# PX4FMUv2_4_6_2.net
KiCad netlist of a schematic drawn in Altium Designer
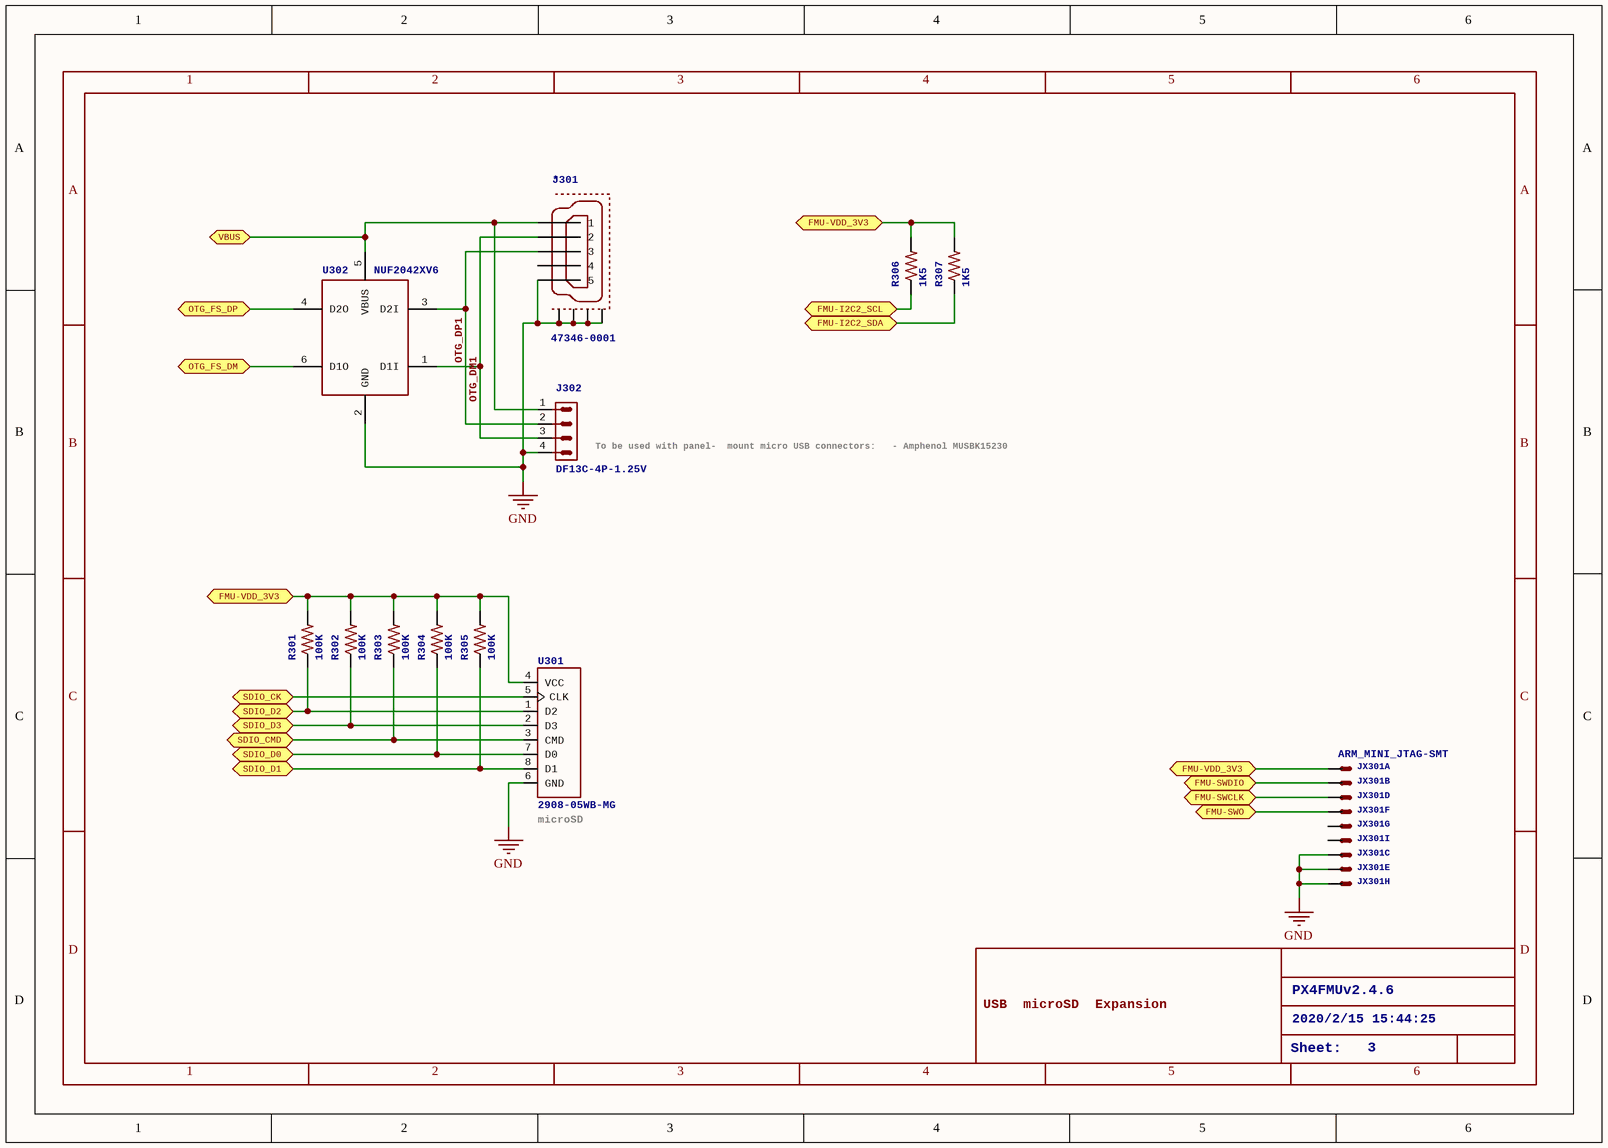
[diagram p0: PX4FMUv2.4.6_2.SchDoc]

(export (version "E")
  (design (tool "Eeschema 10.0.6"))
  (components
    (comp (ref "J301")
      (value "47346-0001")
      (footprint "MOLEX-47346-0001")
      (description "MICRO USB B, BOTTOM MOUNT")
      (fields (field (name "NAME") "*"))
      (libsource (lib "pixhawk2") (part "MOLEX-47346-0001"))
    )
    (comp (ref "J302")
      (value "DF13C-4P-1.25V")
      (footprint "DF13C-4P-1.25V")
      (description "DF13-4P 1.25mm Pitch Miniature Crimping Connector.")
      (fields (field (name "PARTNO") "DF13C-4P-1.25V(20)") (field (name "LIBRARYNAME") "con-hirose-df13"))
      (libsource (lib "con-hirose-df13") (part "DF13-4P-1.25V"))
    )
    (comp (ref "JX301")
      (value "ARM_MINI_JTAG-SMT")
      (footprint "FTSH-105-01-XXX-DV-K")
      (description "CONNECTORwire to board 1.25 mm (.049 inch) pitch header")
      (fields (field (name "PARTNO") "M50-3900542"))
      (libsource (lib "pixhawk2") (part "ARM_MINI_JTAG-SMT"))
    )
    (comp (ref "R301")
      (value "100K")
      (footprint "0402-RES")
      (fields (field (name "PARTNO") "RC0402FR-07100KL"))
      (libsource (lib "pixhawk2") (part "RESISTOR0402-RES"))
    )
    (comp (ref "R302")
      (value "100K")
      (footprint "0402-RES")
      (fields (field (name "PARTNO") "RC0402FR-07100KL"))
      (libsource (lib "pixhawk2") (part "RESISTOR0402-RES"))
    )
    (comp (ref "R303")
      (value "100K")
      (footprint "0402-RES")
      (fields (field (name "PARTNO") "RC0402FR-07100KL"))
      (libsource (lib "pixhawk2") (part "RESISTOR0402-RES"))
    )
    (comp (ref "R304")
      (value "100K")
      (footprint "0402-RES")
      (fields (field (name "PARTNO") "RC0402FR-07100KL"))
      (libsource (lib "pixhawk2") (part "RESISTOR0402-RES"))
    )
    (comp (ref "R305")
      (value "100K")
      (footprint "0402-RES")
      (fields (field (name "PARTNO") "RC0402FR-07100KL"))
      (libsource (lib "pixhawk2") (part "RESISTOR0402-RES"))
    )
    (comp (ref "R306")
      (value "1K5")
      (footprint "0402-RES")
      (fields (field (name "PARTNO") "RC0402FR-071K5L"))
      (libsource (lib "pixhawk2") (part "RESISTOR0402-RES"))
    )
    (comp (ref "R307")
      (value "1K5")
      (footprint "0402-RES")
      (fields (field (name "PARTNO") "RC0402FR-071K5L"))
      (libsource (lib "pixhawk2") (part "RESISTOR0402-RES"))
    )
    (comp (ref "U301")
      (value "2908-05WB-MG")
      (footprint "MICROSD")
      (libsource (lib "baseboard") (part "MICROSDSDI"))
    )
    (comp (ref "U302")
      (value "NUF2042XV6")
      (footprint "SOT563-6")
      (fields (field (name "PARTNO") "NUF2042XV6T1G"))
      (libsource (lib "pixhawk2") (part "NUF2042XV6"))
    )
  )
  (nets
    (net (code "1") (name "/FMU-I2C2_SCL") (class "Default")
      (node (ref "R306") (pin "P$1") (pinfunction "1_P$1") (pintype "passive"))
    )
    (net (code "2") (name "/FMU-I2C2_SDA") (class "Default")
      (node (ref "R307") (pin "P$1") (pinfunction "1_P$1") (pintype "passive"))
    )
    (net (code "3") (name "/FMU-SWCLK") (class "Default")
      (node (ref "JX301") (pin "4") (pinfunction "S_4") (pintype "passive"))
    )
    (net (code "4") (name "/FMU-SWDIO") (class "Default")
      (node (ref "JX301") (pin "2") (pinfunction "S_2") (pintype "passive"))
    )
    (net (code "5") (name "/FMU-SWO") (class "Default")
      (node (ref "JX301") (pin "6") (pinfunction "S_6") (pintype "passive"))
    )
    (net (code "6") (name "/FMU-VDD_3V3") (class "Default")
      (node (ref "JX301") (pin "1") (pinfunction "S_1") (pintype "passive"))
      (node (ref "R301") (pin "P$2") (pinfunction "2_P$2") (pintype "passive"))
      (node (ref "R302") (pin "P$2") (pinfunction "2_P$2") (pintype "passive"))
      (node (ref "R303") (pin "P$2") (pinfunction "2_P$2") (pintype "passive"))
      (node (ref "R304") (pin "P$2") (pinfunction "2_P$2") (pintype "passive"))
      (node (ref "R305") (pin "P$2") (pinfunction "2_P$2") (pintype "passive"))
      (node (ref "R306") (pin "P$2") (pinfunction "2_P$2") (pintype "passive"))
      (node (ref "R307") (pin "P$2") (pinfunction "2_P$2") (pintype "passive"))
      (node (ref "U301") (pin "4") (pinfunction "VCC_4") (pintype "passive"))
    )
    (net (code "7") (name "/OTG_DM1") (class "Default")
      (node (ref "J301") (pin "D-") (pinfunction "2_D-") (pintype "passive"))
      (node (ref "J302") (pin "3") (pinfunction "3_3") (pintype "passive"))
      (node (ref "U302") (pin "1") (pinfunction "D1I_1") (pintype "passive"))
    )
    (net (code "8") (name "/OTG_DP1") (class "Default")
      (node (ref "J301") (pin "D+") (pinfunction "3_D+") (pintype "passive"))
      (node (ref "J302") (pin "2") (pinfunction "2_2") (pintype "passive"))
      (node (ref "U302") (pin "3") (pinfunction "D2I_3") (pintype "passive"))
    )
    (net (code "9") (name "/OTG_FS_DM") (class "Default")
      (node (ref "U302") (pin "6") (pinfunction "D1O_6") (pintype "passive"))
    )
    (net (code "10") (name "/OTG_FS_DP") (class "Default")
      (node (ref "U302") (pin "4") (pinfunction "D2O_4") (pintype "passive"))
    )
    (net (code "11") (name "/SDIO_CK") (class "Default")
      (node (ref "U301") (pin "5") (pinfunction "CLK_5") (pintype "passive"))
    )
    (net (code "12") (name "/SDIO_CMD") (class "Default")
      (node (ref "R303") (pin "P$1") (pinfunction "1_P$1") (pintype "passive"))
      (node (ref "U301") (pin "3") (pinfunction "CMD_3") (pintype "passive"))
    )
    (net (code "13") (name "/SDIO_D0") (class "Default")
      (node (ref "R304") (pin "P$1") (pinfunction "1_P$1") (pintype "passive"))
      (node (ref "U301") (pin "7") (pinfunction "D0_7") (pintype "passive"))
    )
    (net (code "14") (name "/SDIO_D1") (class "Default")
      (node (ref "R305") (pin "P$1") (pinfunction "1_P$1") (pintype "passive"))
      (node (ref "U301") (pin "8") (pinfunction "D1_8") (pintype "passive"))
    )
    (net (code "15") (name "/SDIO_D2") (class "Default")
      (node (ref "R301") (pin "P$1") (pinfunction "1_P$1") (pintype "passive"))
      (node (ref "U301") (pin "1") (pinfunction "D2_1") (pintype "passive"))
    )
    (net (code "16") (name "/SDIO_D3") (class "Default")
      (node (ref "R302") (pin "P$1") (pinfunction "1_P$1") (pintype "passive"))
      (node (ref "U301") (pin "2") (pinfunction "D3_2") (pintype "passive"))
    )
    (net (code "17") (name "/VBUS") (class "Default")
      (node (ref "J301") (pin "VBUS") (pinfunction "1_VBUS") (pintype "open_emitter"))
      (node (ref "J302") (pin "1") (pinfunction "1_1") (pintype "passive"))
      (node (ref "U302") (pin "5") (pinfunction "VBUS_5") (pintype "passive"))
    )
    (net (code "18") (name "GND") (class "Default")
      (node (ref "J301") (pin "GND") (pinfunction "5_GND") (pintype "open_emitter"))
      (node (ref "J301") (pin "GND1") (pinfunction "GND1_GND1") (pintype "passive"))
      (node (ref "J301") (pin "GND2") (pinfunction "GND2_GND2") (pintype "passive"))
      (node (ref "J301") (pin "GND3") (pinfunction "GND3_GND3") (pintype "passive"))
      (node (ref "J301") (pin "GND4") (pinfunction "GND4_GND4") (pintype "passive"))
      (node (ref "J302") (pin "4") (pinfunction "4_4") (pintype "passive"))
      (node (ref "JX301") (pin "3") (pinfunction "S_3") (pintype "passive"))
      (node (ref "JX301") (pin "5") (pinfunction "S_5") (pintype "passive"))
      (node (ref "JX301") (pin "9") (pinfunction "S_9") (pintype "passive"))
      (node (ref "U301") (pin "6") (pinfunction "GND_6") (pintype "open_emitter"))
      (node (ref "U302") (pin "2") (pinfunction "GND_2") (pintype "passive"))
    )
    (net (code "19") (name "unconnected-(J301-4-PadID)") (class "Default")
      (node (ref "J301") (pin "ID") (pinfunction "4_ID") (pintype "passive"))
    )
    (net (code "20") (name "unconnected-(JX301G-S-Pad8)") (class "Default")
      (node (ref "JX301") (pin "8") (pinfunction "S_8") (pintype "passive"))
    )
    (net (code "21") (name "unconnected-(JX301I-S-Pad10)") (class "Default")
      (node (ref "JX301") (pin "10") (pinfunction "S_10") (pintype "passive"))
    )
  )
)
